# Adafruit_VS1053_Amp_FeatherWing.net
KiCad netlist of a schematic drawn in EAGLE
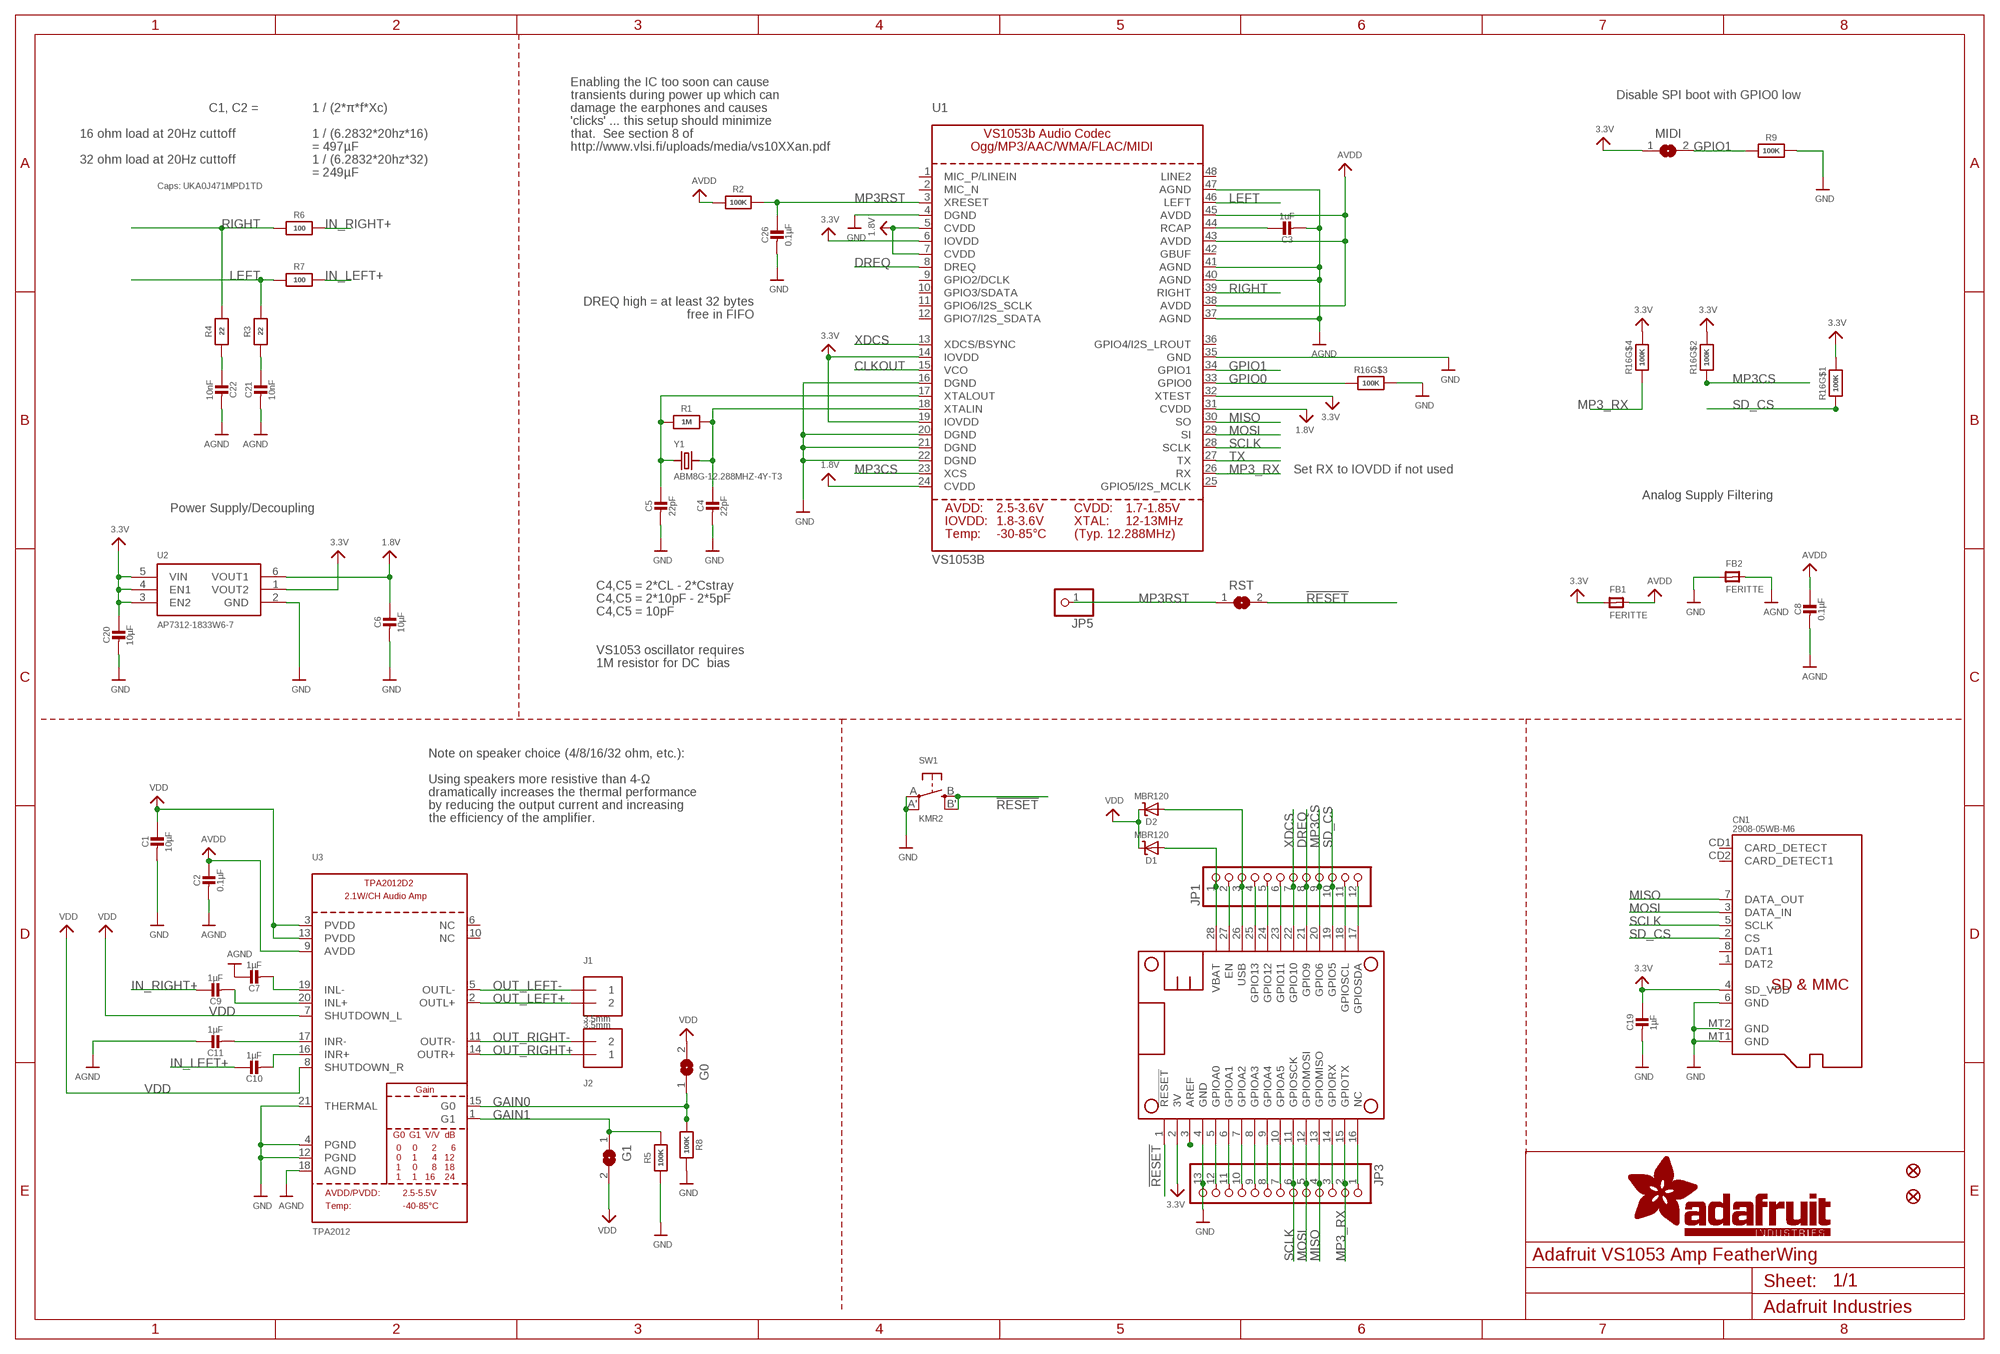
[diagram p0: schematic, sheet 1]

(export (version "E")
  (design (tool "Eeschema 10.0.6"))
  (components
    (comp (ref "C1")
      (value "10µF")
      (footprint "eagle-import:0805-NO")
      (libsource (lib "eagle-import") (part "CAP_CERAMIC0805-NOOUTLINE"))
    )
    (comp (ref "C2")
      (value "0.1µF")
      (footprint "eagle-import:0603-NO")
      (libsource (lib "eagle-import") (part "CAP_CERAMIC0603_NO"))
    )
    (comp (ref "C3")
      (value "1uF")
      (footprint "eagle-import:0603-NO")
      (libsource (lib "eagle-import") (part "CAP_CERAMIC0603_NO"))
    )
    (comp (ref "C4")
      (value "22pF")
      (footprint "eagle-import:0603-NO")
      (libsource (lib "eagle-import") (part "CAP_CERAMIC0603_NO"))
    )
    (comp (ref "C5")
      (value "22pF")
      (footprint "eagle-import:0603-NO")
      (libsource (lib "eagle-import") (part "CAP_CERAMIC0603_NO"))
    )
    (comp (ref "C6")
      (value "10µF")
      (footprint "eagle-import:_0805MP")
      (libsource (lib "eagle-import") (part "CAP_CERAMIC_0805MP"))
    )
    (comp (ref "C7")
      (value "1µF")
      (footprint "eagle-import:0603-NO")
      (libsource (lib "eagle-import") (part "CAP_CERAMIC0603_NO"))
    )
    (comp (ref "C8")
      (value "0.1µF")
      (footprint "eagle-import:0603-NO")
      (libsource (lib "eagle-import") (part "CAP_CERAMIC0603_NO"))
    )
    (comp (ref "C9")
      (value "1µF")
      (footprint "eagle-import:0603-NO")
      (libsource (lib "eagle-import") (part "CAP_CERAMIC0603_NO"))
    )
    (comp (ref "C10")
      (value "1µF")
      (footprint "eagle-import:0603-NO")
      (libsource (lib "eagle-import") (part "CAP_CERAMIC0603_NO"))
    )
    (comp (ref "C11")
      (value "1µF")
      (footprint "eagle-import:0603-NO")
      (libsource (lib "eagle-import") (part "CAP_CERAMIC0603_NO"))
    )
    (comp (ref "C19")
      (value "1µF")
      (footprint "eagle-import:0603-NO")
      (libsource (lib "eagle-import") (part "CAP_CERAMIC0603_NO"))
    )
    (comp (ref "C20")
      (value "10µF")
      (footprint "eagle-import:0805-NO")
      (libsource (lib "eagle-import") (part "CAP_CERAMIC0805-NOOUTLINE"))
    )
    (comp (ref "C21")
      (value "10nF")
      (footprint "eagle-import:0603-NO")
      (libsource (lib "eagle-import") (part "CAP_CERAMIC0603_NO"))
    )
    (comp (ref "C22")
      (value "10nF")
      (footprint "eagle-import:0603-NO")
      (libsource (lib "eagle-import") (part "CAP_CERAMIC0603_NO"))
    )
    (comp (ref "C26")
      (value "0.1µF")
      (footprint "eagle-import:0603-NO")
      (libsource (lib "eagle-import") (part "CAP_CERAMIC0603_NO"))
    )
    (comp (ref "CN1")
      (value "2908-05WB-M6")
      (footprint "eagle-import:MICROSD")
      (libsource (lib "eagle-import") (part "MICROSD"))
    )
    (comp (ref "D1")
      (value "MBR120")
      (footprint "eagle-import:SOD-123")
      (libsource (lib "eagle-import") (part "DIODE-SCHOTTKYSOD-123"))
    )
    (comp (ref "D2")
      (value "MBR120")
      (footprint "eagle-import:SOD-123")
      (libsource (lib "eagle-import") (part "DIODE-SCHOTTKYSOD-123"))
    )
    (comp (ref "FB1")
      (value "FERITTE")
      (footprint "eagle-import:0805-NO")
      (libsource (lib "eagle-import") (part "FERRITE-0805NO"))
    )
    (comp (ref "FB2")
      (value "FERITTE")
      (footprint "eagle-import:0805-NO")
      (libsource (lib "eagle-import") (part "FERRITE-0805NO"))
    )
    (comp (ref "FID1")
      (value "FIDUCIAL\"\"")
      (footprint "eagle-import:FIDUCIAL_1MM")
      (libsource (lib "eagle-import") (part "FIDUCIAL{dblquote}{dblquote}"))
    )
    (comp (ref "FID2")
      (value "FIDUCIAL\"\"")
      (footprint "eagle-import:FIDUCIAL_1MM")
      (libsource (lib "eagle-import") (part "FIDUCIAL{dblquote}{dblquote}"))
    )
    (comp (ref "G0")
      (value "SOLDERJUMPER")
      (footprint "eagle-import:SOLDERJUMPER_ARROW_NOPASTE")
      (libsource (lib "eagle-import") (part "SOLDERJUMPER"))
    )
    (comp (ref "G1")
      (value "SOLDERJUMPER")
      (footprint "eagle-import:SOLDERJUMPER_ARROW_NOPASTE")
      (libsource (lib "eagle-import") (part "SOLDERJUMPER"))
    )
    (comp (ref "J1")
      (value "3.5mm")
      (footprint "eagle-import:TERMBLOCK_1X2-3.5MM")
      (libsource (lib "eagle-import") (part "TERMBLOCK_1X2"))
    )
    (comp (ref "J2")
      (value "3.5mm")
      (footprint "eagle-import:TERMBLOCK_1X2-3.5MM")
      (libsource (lib "eagle-import") (part "TERMBLOCK_1X2"))
    )
    (comp (ref "JP1")
      (value "HEADER-1X12")
      (footprint "eagle-import:1X12_ROUND")
      (libsource (lib "eagle-import") (part "HEADER-1X12"))
    )
    (comp (ref "JP3")
      (value "HEADER-1X13")
      (footprint "eagle-import:1X13_ROUND_70")
      (libsource (lib "eagle-import") (part "HEADER-1X13"))
    )
    (comp (ref "JP5")
      (value "HEADER-1X1ROUND")
      (footprint "eagle-import:1X01_ROUND")
      (libsource (lib "eagle-import") (part "HEADER-1X1ROUND"))
    )
    (comp (ref "MIDI")
      (value "SOLDERJUMPER")
      (footprint "eagle-import:SOLDERJUMPER_ARROW_NOPASTE")
      (libsource (lib "eagle-import") (part "SOLDERJUMPER"))
    )
    (comp (ref "MS1")
      (value "FEATHERWING_NODIM")
      (footprint "eagle-import:FEATHERWING_NODIM")
      (libsource (lib "eagle-import") (part "FEATHERWING_NODIM"))
    )
    (comp (ref "R1")
      (value "1M")
      (footprint "eagle-import:0603-NO")
      (libsource (lib "eagle-import") (part "RESISTOR_0603_NOOUT"))
    )
    (comp (ref "R2")
      (value "100K")
      (footprint "eagle-import:0603-NO")
      (libsource (lib "eagle-import") (part "RESISTOR_0603_NOOUT"))
    )
    (comp (ref "R3")
      (value "22")
      (footprint "eagle-import:0603-NO")
      (libsource (lib "eagle-import") (part "RESISTOR_0603_NOOUT"))
    )
    (comp (ref "R4")
      (value "22")
      (footprint "eagle-import:0603-NO")
      (libsource (lib "eagle-import") (part "RESISTOR_0603_NOOUT"))
    )
    (comp (ref "R5")
      (value "100K")
      (footprint "eagle-import:0603-NO")
      (libsource (lib "eagle-import") (part "RESISTOR_0603_NOOUT"))
    )
    (comp (ref "R6")
      (value "100")
      (footprint "eagle-import:0603-NO")
      (libsource (lib "eagle-import") (part "RESISTOR_0603_NOOUT"))
    )
    (comp (ref "R7")
      (value "100")
      (footprint "eagle-import:0603-NO")
      (libsource (lib "eagle-import") (part "RESISTOR_0603_NOOUT"))
    )
    (comp (ref "R8")
      (value "100K")
      (footprint "eagle-import:0603-NO")
      (libsource (lib "eagle-import") (part "RESISTOR_0603_NOOUT"))
    )
    (comp (ref "R9")
      (value "100K")
      (footprint "eagle-import:_0603MP")
      (libsource (lib "eagle-import") (part "RESISTOR_0603MP"))
    )
    (comp (ref "R16")
      (value "100K")
      (footprint "eagle-import:RESPACK_4X0603")
      (libsource (lib "eagle-import") (part "RESISTOR_4PACK"))
    )
    (comp (ref "RST")
      (value "SOLDERJUMPERCLOSED")
      (footprint "eagle-import:SOLDERJUMPER_CLOSEDWIRE")
      (libsource (lib "eagle-import") (part "SOLDERJUMPERCLOSED"))
    )
    (comp (ref "SW1")
      (value "KMR2")
      (footprint "eagle-import:BTN_KMR2_4.6X2.8")
      (libsource (lib "eagle-import") (part "SWITCH_TACT_SMT4.6X2.8"))
    )
    (comp (ref "U1")
      (value "VS1053B")
      (footprint "eagle-import:LQFP48")
      (libsource (lib "eagle-import") (part "VS1053B"))
    )
    (comp (ref "U2")
      (value "AP7312-1833W6-7")
      (footprint "eagle-import:SOT23-6")
      (libsource (lib "eagle-import") (part "VREG_SOT23-6_DUALAP7312"))
    )
    (comp (ref "U3")
      (value "TPA2012")
      (footprint "eagle-import:WQFN20")
      (libsource (lib "eagle-import") (part "AUDIOAMP_TPA2012D2"))
    )
    (comp (ref "Y1")
      (value "ABM8G-12.288MHZ-4Y-T3")
      (footprint "eagle-import:CRYSTAL_3.2X2.5")
      (libsource (lib "eagle-import") (part "CRYSTAL3.2X2.5"))
    )
  )
  (nets
    (net (code "1") (name "/CLKOUT") (class "Default")
      (node (ref "U1") (pin "15") (pinfunction "VCO_15") (pintype "bidirectional"))
    )
    (net (code "2") (name "/DREQ") (class "Default")
      (node (ref "JP1") (pin "8") (pinfunction "8_8") (pintype "passive"))
      (node (ref "MS1") (pin "21") (pinfunction "GPIO9_21") (pintype "bidirectional"))
      (node (ref "U1") (pin "8") (pinfunction "DREQ_8") (pintype "bidirectional"))
    )
    (net (code "3") (name "/GAIN0") (class "Default")
      (node (ref "G0") (pin "1") (pinfunction "1_1") (pintype "passive"))
      (node (ref "R8") (pin "1") (pinfunction "1_1") (pintype "passive"))
      (node (ref "U3") (pin "15") (pinfunction "G0_15") (pintype "input"))
    )
    (net (code "4") (name "/GAIN1") (class "Default")
      (node (ref "G1") (pin "1") (pinfunction "1_1") (pintype "passive"))
      (node (ref "R5") (pin "2") (pinfunction "2_2") (pintype "passive"))
      (node (ref "U3") (pin "1") (pinfunction "G1_1") (pintype "input"))
    )
    (net (code "5") (name "/GPIO0") (class "Default")
      (node (ref "R16") (pin "3") (pinfunction "1_3") (pintype "passive"))
      (node (ref "U1") (pin "33") (pinfunction "GPIO0_33") (pintype "bidirectional"))
    )
    (net (code "6") (name "/GPIO1") (class "Default")
      (node (ref "MIDI") (pin "2") (pinfunction "2_2") (pintype "passive"))
      (node (ref "R9") (pin "1") (pinfunction "1_1") (pintype "passive"))
      (node (ref "U1") (pin "34") (pinfunction "GPIO1_34") (pintype "bidirectional"))
    )
    (net (code "7") (name "/IN_LEFT+") (class "Default")
      (node (ref "C10") (pin "1") (pinfunction "1_1") (pintype "passive"))
      (node (ref "R7") (pin "1") (pinfunction "1_1") (pintype "passive"))
    )
    (net (code "8") (name "/IN_RIGHT+") (class "Default")
      (node (ref "C9") (pin "1") (pinfunction "1_1") (pintype "passive"))
      (node (ref "R6") (pin "1") (pinfunction "1_1") (pintype "passive"))
    )
    (net (code "9") (name "/LEFT") (class "Default")
      (node (ref "R3") (pin "1") (pinfunction "1_1") (pintype "passive"))
      (node (ref "R7") (pin "2") (pinfunction "2_2") (pintype "passive"))
      (node (ref "U1") (pin "46") (pinfunction "LEFT_46") (pintype "bidirectional"))
    )
    (net (code "10") (name "/MISO") (class "Default")
      (node (ref "CN1") (pin "7") (pinfunction "DATA_OUT_7") (pintype "output"))
      (node (ref "JP3") (pin "4") (pinfunction "4_4") (pintype "passive"))
      (node (ref "MS1") (pin "13") (pinfunction "GPIOMISO_13") (pintype "bidirectional"))
      (node (ref "U1") (pin "30") (pinfunction "SO_30") (pintype "bidirectional"))
    )
    (net (code "11") (name "/MOSI") (class "Default")
      (node (ref "CN1") (pin "3") (pinfunction "DATA_IN_3") (pintype "input"))
      (node (ref "JP3") (pin "5") (pinfunction "5_5") (pintype "passive"))
      (node (ref "MS1") (pin "12") (pinfunction "GPIOMOSI_12") (pintype "bidirectional"))
      (node (ref "U1") (pin "29") (pinfunction "SI_29") (pintype "bidirectional"))
    )
    (net (code "12") (name "/MP3CS") (class "Default")
      (node (ref "JP1") (pin "9") (pinfunction "9_9") (pintype "passive"))
      (node (ref "MS1") (pin "20") (pinfunction "GPIO6_20") (pintype "bidirectional"))
      (node (ref "R16") (pin "2") (pinfunction "1_2") (pintype "passive"))
      (node (ref "U1") (pin "23") (pinfunction "XCS_23") (pintype "bidirectional"))
    )
    (net (code "13") (name "/MP3RST") (class "Default")
      (node (ref "C26") (pin "1") (pinfunction "1_1") (pintype "passive"))
      (node (ref "JP5") (pin "1") (pinfunction "1_1") (pintype "passive"))
      (node (ref "R2") (pin "2") (pinfunction "2_2") (pintype "passive"))
      (node (ref "RST") (pin "1") (pinfunction "1_1") (pintype "passive"))
      (node (ref "U1") (pin "3") (pinfunction "XRESET_3") (pintype "bidirectional"))
    )
    (net (code "14") (name "/MP3_RX") (class "Default")
      (node (ref "JP3") (pin "2") (pinfunction "2_2") (pintype "passive"))
      (node (ref "MS1") (pin "15") (pinfunction "GPIOTX_15") (pintype "bidirectional"))
      (node (ref "R16") (pin "4") (pinfunction "1_4") (pintype "passive"))
      (node (ref "U1") (pin "26") (pinfunction "RX_26") (pintype "bidirectional"))
    )
    (net (code "15") (name "/OUT_LEFT+") (class "Default")
      (node (ref "J1") (pin "2") (pinfunction "2_2") (pintype "passive"))
      (node (ref "U3") (pin "2") (pinfunction "OUTL+_2") (pintype "output"))
    )
    (net (code "16") (name "/OUT_LEFT-") (class "Default")
      (node (ref "J1") (pin "1") (pinfunction "1_1") (pintype "passive"))
      (node (ref "U3") (pin "5") (pinfunction "OUTL-_5") (pintype "output"))
    )
    (net (code "17") (name "/OUT_RIGHT+") (class "Default")
      (node (ref "J2") (pin "1") (pinfunction "1_1") (pintype "passive"))
      (node (ref "U3") (pin "14") (pinfunction "OUTR+_14") (pintype "output"))
    )
    (net (code "18") (name "/OUT_RIGHT-") (class "Default")
      (node (ref "J2") (pin "2") (pinfunction "2_2") (pintype "passive"))
      (node (ref "U3") (pin "11") (pinfunction "OUTR-_11") (pintype "output"))
    )
    (net (code "19") (name "/RIGHT") (class "Default")
      (node (ref "R4") (pin "1") (pinfunction "1_1") (pintype "passive"))
      (node (ref "R6") (pin "2") (pinfunction "2_2") (pintype "passive"))
      (node (ref "U1") (pin "39") (pinfunction "RIGHT_39") (pintype "bidirectional"))
    )
    (net (code "20") (name "/SCLK") (class "Default")
      (node (ref "CN1") (pin "5") (pinfunction "SCLK_5") (pintype "input"))
      (node (ref "JP3") (pin "6") (pinfunction "6_6") (pintype "passive"))
      (node (ref "MS1") (pin "11") (pinfunction "GPIOSCK_11") (pintype "bidirectional"))
      (node (ref "U1") (pin "28") (pinfunction "SCLK_28") (pintype "bidirectional"))
    )
    (net (code "21") (name "/SD_CS") (class "Default")
      (node (ref "CN1") (pin "2") (pinfunction "CS_2") (pintype "input"))
      (node (ref "JP1") (pin "10") (pinfunction "10_10") (pintype "passive"))
      (node (ref "MS1") (pin "19") (pinfunction "GPIO5_19") (pintype "bidirectional"))
      (node (ref "R16") (pin "1") (pinfunction "1_1") (pintype "passive"))
    )
    (net (code "22") (name "/TX") (class "Default")
      (node (ref "U1") (pin "27") (pinfunction "TX_27") (pintype "bidirectional"))
    )
    (net (code "23") (name "/XDCS") (class "Default")
      (node (ref "JP1") (pin "7") (pinfunction "7_7") (pintype "passive"))
      (node (ref "MS1") (pin "22") (pinfunction "GPIO10_22") (pintype "bidirectional"))
      (node (ref "U1") (pin "13") (pinfunction "XDCS/BSYNC_13") (pintype "bidirectional"))
    )
    (net (code "24") (name "/~{RESET}") (class "Default")
      (node (ref "MS1") (pin "1") (pinfunction "~{RESET}_1") (pintype "input"))
      (node (ref "RST") (pin "2") (pinfunction "2_2") (pintype "passive"))
      (node (ref "SW1") (pin "B") (pinfunction "S_B") (pintype "passive"))
      (node (ref "SW1") (pin "B'") (pinfunction "S1_B'") (pintype "passive"))
    )
    (net (code "25") (name "1.8V") (class "Default")
      (node (ref "C6") (pin "1") (pinfunction "1_1") (pintype "passive"))
      (node (ref "U1") (pin "24") (pinfunction "CVDD_24") (pintype "power_in"))
      (node (ref "U1") (pin "31") (pinfunction "CVDD_31") (pintype "power_in"))
      (node (ref "U1") (pin "5") (pinfunction "CVDD_5") (pintype "power_in"))
      (node (ref "U1") (pin "7") (pinfunction "CVDD_7") (pintype "power_in"))
      (node (ref "U2") (pin "6") (pinfunction "VOUT1_6") (pintype "bidirectional"))
    )
    (net (code "26") (name "3.3V") (class "Default")
      (node (ref "C19") (pin "1") (pinfunction "1_1") (pintype "passive"))
      (node (ref "C20") (pin "1") (pinfunction "1_1") (pintype "passive"))
      (node (ref "CN1") (pin "4") (pinfunction "SD_VDD_4") (pintype "power_in"))
      (node (ref "FB1") (pin "1") (pinfunction "P$1_1") (pintype "passive"))
      (node (ref "MIDI") (pin "1") (pinfunction "1_1") (pintype "passive"))
      (node (ref "MS1") (pin "2") (pinfunction "3V_2") (pintype "power_in"))
      (node (ref "R16") (pin "5") (pinfunction "2_5") (pintype "passive"))
      (node (ref "R16") (pin "7") (pinfunction "2_7") (pintype "passive"))
      (node (ref "R16") (pin "8") (pinfunction "2_8") (pintype "passive"))
      (node (ref "U1") (pin "14") (pinfunction "IOVDD_14") (pintype "power_in"))
      (node (ref "U1") (pin "19") (pinfunction "IOVDD_19") (pintype "power_in"))
      (node (ref "U1") (pin "32") (pinfunction "XTEST_32") (pintype "bidirectional"))
      (node (ref "U1") (pin "6") (pinfunction "IOVDD_6") (pintype "power_in"))
      (node (ref "U2") (pin "1") (pinfunction "VOUT2_1") (pintype "bidirectional"))
      (node (ref "U2") (pin "3") (pinfunction "EN2_3") (pintype "bidirectional"))
      (node (ref "U2") (pin "4") (pinfunction "EN1_4") (pintype "bidirectional"))
      (node (ref "U2") (pin "5") (pinfunction "VIN_5") (pintype "bidirectional"))
    )
    (net (code "27") (name "AGND") (class "Default")
      (node (ref "C11") (pin "1") (pinfunction "1_1") (pintype "passive"))
      (node (ref "C2") (pin "2") (pinfunction "2_2") (pintype "passive"))
      (node (ref "C21") (pin "2") (pinfunction "2_2") (pintype "passive"))
      (node (ref "C22") (pin "2") (pinfunction "2_2") (pintype "passive"))
      (node (ref "C3") (pin "2") (pinfunction "2_2") (pintype "passive"))
      (node (ref "C7") (pin "1") (pinfunction "1_1") (pintype "passive"))
      (node (ref "C8") (pin "2") (pinfunction "2_2") (pintype "passive"))
      (node (ref "FB2") (pin "2") (pinfunction "P$2_2") (pintype "passive"))
      (node (ref "U1") (pin "37") (pinfunction "AGND_37") (pintype "power_in"))
      (node (ref "U1") (pin "40") (pinfunction "AGND_40") (pintype "power_in"))
      (node (ref "U1") (pin "41") (pinfunction "AGND_41") (pintype "power_in"))
      (node (ref "U1") (pin "47") (pinfunction "AGND_47") (pintype "power_in"))
      (node (ref "U3") (pin "18") (pinfunction "AGND_18") (pintype "power_in"))
    )
    (net (code "28") (name "AVDD") (class "Default")
      (node (ref "C2") (pin "1") (pinfunction "1_1") (pintype "passive"))
      (node (ref "C8") (pin "1") (pinfunction "1_1") (pintype "passive"))
      (node (ref "FB1") (pin "2") (pinfunction "P$2_2") (pintype "passive"))
      (node (ref "R2") (pin "1") (pinfunction "1_1") (pintype "passive"))
      (node (ref "U1") (pin "38") (pinfunction "AVDD_38") (pintype "power_in"))
      (node (ref "U1") (pin "43") (pinfunction "AVDD_43") (pintype "power_in"))
      (node (ref "U1") (pin "45") (pinfunction "AVDD_45") (pintype "power_in"))
      (node (ref "U3") (pin "9") (pinfunction "AVDD_9") (pintype "power_in"))
    )
    (net (code "29") (name "GND") (class "Default")
      (node (ref "C1") (pin "2") (pinfunction "2_2") (pintype "passive"))
      (node (ref "C19") (pin "2") (pinfunction "2_2") (pintype "passive"))
      (node (ref "C20") (pin "2") (pinfunction "2_2") (pintype "passive"))
      (node (ref "C26") (pin "2") (pinfunction "2_2") (pintype "passive"))
      (node (ref "C4") (pin "2") (pinfunction "2_2") (pintype "passive"))
      (node (ref "C5") (pin "2") (pinfunction "2_2") (pintype "passive"))
      (node (ref "C6") (pin "2") (pinfunction "2_2") (pintype "passive"))
      (node (ref "CN1") (pin "6") (pinfunction "GND_6") (pintype "power_in"))
      (node (ref "CN1") (pin "MT1") (pinfunction "GND_MT1") (pintype "power_in"))
      (node (ref "CN1") (pin "MT2") (pinfunction "GND_MT2") (pintype "power_in"))
      (node (ref "FB2") (pin "1") (pinfunction "P$1_1") (pintype "passive"))
      (node (ref "JP3") (pin "13") (pinfunction "13_13") (pintype "passive"))
      (node (ref "MS1") (pin "4") (pinfunction "GND_4") (pintype "power_in"))
      (node (ref "R16") (pin "6") (pinfunction "2_6") (pintype "passive"))
      (node (ref "R5") (pin "1") (pinfunction "1_1") (pintype "passive"))
      (node (ref "R8") (pin "2") (pinfunction "2_2") (pintype "passive"))
      (node (ref "R9") (pin "2") (pinfunction "2_2") (pintype "passive"))
      (node (ref "SW1") (pin "A") (pinfunction "P_A") (pintype "passive"))
      (node (ref "SW1") (pin "A'") (pinfunction "P1_A'") (pintype "passive"))
      (node (ref "U1") (pin "16") (pinfunction "DGND_16") (pintype "power_in"))
      (node (ref "U1") (pin "20") (pinfunction "DGND_20") (pintype "power_in"))
      (node (ref "U1") (pin "21") (pinfunction "DGND_21") (pintype "power_in"))
      (node (ref "U1") (pin "22") (pinfunction "DGND_22") (pintype "power_in"))
      (node (ref "U1") (pin "35") (pinfunction "GND_35") (pintype "power_in"))
      (node (ref "U1") (pin "4") (pinfunction "DGND_4") (pintype "power_in"))
      (node (ref "U2") (pin "2") (pinfunction "GND_2") (pintype "bidirectional"))
      (node (ref "U3") (pin "12") (pinfunction "PGND_12") (pintype "power_in"))
      (node (ref "U3") (pin "21") (pinfunction "THERMAL_21") (pintype "bidirectional"))
      (node (ref "U3") (pin "4") (pinfunction "PGND_4") (pintype "power_in"))
    )
    (net (code "30") (name "Net-(C21-Pad1)") (class "Default")
      (node (ref "C21") (pin "1") (pinfunction "1_1") (pintype "passive"))
      (node (ref "R3") (pin "2") (pinfunction "2_2") (pintype "passive"))
    )
    (net (code "31") (name "Net-(C22-Pad1)") (class "Default")
      (node (ref "C22") (pin "1") (pinfunction "1_1") (pintype "passive"))
      (node (ref "R4") (pin "2") (pinfunction "2_2") (pintype "passive"))
    )
    (net (code "32") (name "Net-(MS1-EN)") (class "Default")
      (node (ref "JP1") (pin "2") (pinfunction "2_2") (pintype "passive"))
      (node (ref "MS1") (pin "27") (pinfunction "EN_27") (pintype "passive"))
    )
    (net (code "33") (name "Net-(MS1-GPIO11)") (class "Default")
      (node (ref "JP1") (pin "6") (pinfunction "6_6") (pintype "passive"))
      (node (ref "MS1") (pin "23") (pinfunction "GPIO11_23") (pintype "bidirectional"))
    )
    (net (code "34") (name "Net-(MS1-GPIO12)") (class "Default")
      (node (ref "JP1") (pin "5") (pinfunction "5_5") (pintype "passive"))
      (node (ref "MS1") (pin "24") (pinfunction "GPIO12_24") (pintype "bidirectional"))
    )
    (net (code "35") (name "Net-(MS1-GPIO13)") (class "Default")
      (node (ref "JP1") (pin "4") (pinfunction "4_4") (pintype "passive"))
      (node (ref "MS1") (pin "25") (pinfunction "GPIO13_25") (pintype "bidirectional"))
    )
    (net (code "36") (name "Net-(MS1-GPIOA0)") (class "Default")
      (node (ref "JP3") (pin "12") (pinfunction "12_12") (pintype "passive"))
      (node (ref "MS1") (pin "5") (pinfunction "GPIOA0_5") (pintype "bidirectional"))
    )
    (net (code "37") (name "Net-(MS1-GPIOA1)") (class "Default")
      (node (ref "JP3") (pin "11") (pinfunction "11_11") (pintype "passive"))
      (node (ref "MS1") (pin "6") (pinfunction "GPIOA1_6") (pintype "bidirectional"))
    )
    (net (code "38") (name "Net-(MS1-GPIOA2)") (class "Default")
      (node (ref "JP3") (pin "10") (pinfunction "10_10") (pintype "passive"))
      (node (ref "MS1") (pin "7") (pinfunction "GPIOA2_7") (pintype "bidirectional"))
    )
    (net (code "39") (name "Net-(MS1-GPIOA3)") (class "Default")
      (node (ref "JP3") (pin "9") (pinfunction "9_9") (pintype "passive"))
      (node (ref "MS1") (pin "8") (pinfunction "GPIOA3_8") (pintype "bidirectional"))
    )
    (net (code "40") (name "Net-(MS1-GPIOA4)") (class "Default")
      (node (ref "JP3") (pin "8") (pinfunction "8_8") (pintype "passive"))
      (node (ref "MS1") (pin "9") (pinfunction "GPIOA4_9") (pintype "bidirectional"))
    )
    (net (code "41") (name "Net-(MS1-GPIOA5)") (class "Default")
      (node (ref "JP3") (pin "7") (pinfunction "7_7") (pintype "passive"))
      (node (ref "MS1") (pin "10") (pinfunction "GPIOA5_10") (pintype "bidirectional"))
    )
    (net (code "42") (name "Net-(MS1-GPIORX)") (class "Default")
      (node (ref "JP3") (pin "3") (pinfunction "3_3") (pintype "passive"))
      (node (ref "MS1") (pin "14") (pinfunction "GPIORX_14") (pintype "bidirectional"))
    )
    (net (code "43") (name "Net-(MS1-GPIOSCL)") (class "Default")
      (node (ref "JP1") (pin "11") (pinfunction "11_11") (pintype "passive"))
      (node (ref "MS1") (pin "18") (pinfunction "GPIOSCL_18") (pintype "bidirectional"))
    )
    (net (code "44") (name "Net-(MS1-GPIOSDA)") (class "Default")
      (node (ref "JP1") (pin "12") (pinfunction "12_12") (pintype "passive"))
      (node (ref "MS1") (pin "17") (pinfunction "GPIOSDA_17") (pintype "bidirectional"))
    )
    (net (code "45") (name "Net-(MS1-NC)") (class "Default")
      (node (ref "JP3") (pin "1") (pinfunction "1_1") (pintype "passive"))
      (node (ref "MS1") (pin "16") (pinfunction "NC_16") (pintype "passive"))
    )
    (net (code "46") (name "Net-(MS1-USB)") (class "Default")
      (node (ref "D2") (pin "A") (pinfunction "A_A") (pintype "passive"))
      (node (ref "JP1") (pin "3") (pinfunction "3_3") (pintype "passive"))
      (node (ref "MS1") (pin "26") (pinfunction "USB_26") (pintype "power_in"))
    )
    (net (code "47") (name "Net-(MS1-VBAT)") (class "Default")
      (node (ref "D1") (pin "A") (pinfunction "A_A") (pintype "passive"))
      (node (ref "JP1") (pin "1") (pinfunction "1_1") (pintype "passive"))
      (node (ref "MS1") (pin "28") (pinfunction "VBAT_28") (pintype "power_in"))
    )
    (net (code "48") (name "Net-(U1-RCAP)") (class "Default")
      (node (ref "C3") (pin "1") (pinfunction "1_1") (pintype "passive"))
      (node (ref "U1") (pin "44") (pinfunction "RCAP_44") (pintype "bidirectional"))
    )
    (net (code "49") (name "Net-(U1-XTALIN)") (class "Default")
      (node (ref "C4") (pin "1") (pinfunction "1_1") (pintype "passive"))
      (node (ref "R1") (pin "2") (pinfunction "2_2") (pintype "passive"))
      (node (ref "U1") (pin "18") (pinfunction "XTALIN_18") (pintype "input"))
      (node (ref "Y1") (pin "2") (pinfunction "2_2") (pintype "passive"))
    )
    (net (code "50") (name "Net-(U1-XTALOUT)") (class "Default")
      (node (ref "C5") (pin "1") (pinfunction "1_1") (pintype "passive"))
      (node (ref "R1") (pin "1") (pinfunction "1_1") (pintype "passive"))
      (node (ref "U1") (pin "17") (pinfunction "XTALOUT_17") (pintype "output"))
      (node (ref "Y1") (pin "1") (pinfunction "1_1") (pintype "passive"))
    )
    (net (code "51") (name "Net-(U3-INL+)") (class "Default")
      (node (ref "C9") (pin "2") (pinfunction "2_2") (pintype "passive"))
      (node (ref "U3") (pin "20") (pinfunction "INL+_20") (pintype "input"))
    )
    (net (code "52") (name "Net-(U3-INL-)") (class "Default")
      (node (ref "C7") (pin "2") (pinfunction "2_2") (pintype "passive"))
      (node (ref "U3") (pin "19") (pinfunction "INL-_19") (pintype "input"))
    )
    (net (code "53") (name "Net-(U3-INR+)") (class "Default")
      (node (ref "C10") (pin "2") (pinfunction "2_2") (pintype "passive"))
      (node (ref "U3") (pin "16") (pinfunction "INR+_16") (pintype "input"))
    )
    (net (code "54") (name "Net-(U3-INR-)") (class "Default")
      (node (ref "C11") (pin "2") (pinfunction "2_2") (pintype "passive"))
      (node (ref "U3") (pin "17") (pinfunction "INR-_17") (pintype "input"))
    )
    (net (code "55") (name "VDD") (class "Default")
      (node (ref "C1") (pin "1") (pinfunction "1_1") (pintype "passive"))
      (node (ref "D1") (pin "C") (pinfunction "C_C") (pintype "passive"))
      (node (ref "D2") (pin "C") (pinfunction "C_C") (pintype "passive"))
      (node (ref "G0") (pin "2") (pinfunction "2_2") (pintype "passive"))
      (node (ref "G1") (pin "2") (pinfunction "2_2") (pintype "passive"))
      (node (ref "U3") (pin "13") (pinfunction "PVDD_13") (pintype "power_in"))
      (node (ref "U3") (pin "3") (pinfunction "PVDD_3") (pintype "power_in"))
      (node (ref "U3") (pin "7") (pinfunction "SHUTDOWN_L_7") (pintype "input"))
      (node (ref "U3") (pin "8") (pinfunction "SHUTDOWN_R_8") (pintype "input"))
    )
    (net (code "56") (name "unconnected-(CN1-CARD_DETECT-PadCD1)") (class "Default")
      (node (ref "CN1") (pin "CD1") (pinfunction "CARD_DETECT_CD1") (pintype "passive"))
    )
    (net (code "57") (name "unconnected-(CN1-CARD_DETECT1-PadCD2)") (class "Default")
      (node (ref "CN1") (pin "CD2") (pinfunction "CARD_DETECT1_CD2") (pintype "passive"))
    )
    (net (code "58") (name "unconnected-(CN1-DAT1-Pad8)") (class "Default")
      (node (ref "CN1") (pin "8") (pinfunction "DAT1_8") (pintype "bidirectional"))
    )
    (net (code "59") (name "unconnected-(CN1-DAT2-Pad1)") (class "Default")
      (node (ref "CN1") (pin "1") (pinfunction "DAT2_1") (pintype "bidirectional"))
    )
    (net (code "60") (name "unconnected-(MS1-AREF-Pad3)") (class "Default")
      (node (ref "MS1") (pin "3") (pinfunction "AREF_3") (pintype "passive"))
    )
    (net (code "61") (name "unconnected-(U1-GBUF-Pad42)") (class "Default")
      (node (ref "U1") (pin "42") (pinfunction "GBUF_42") (pintype "bidirectional"))
    )
    (net (code "62") (name "unconnected-(U1-GPIO2{slash}DCLK-Pad9)") (class "Default")
      (node (ref "U1") (pin "9") (pinfunction "GPIO2/DCLK_9") (pintype "bidirectional"))
    )
    (net (code "63") (name "unconnected-(U1-GPIO3{slash}SDATA-Pad10)") (class "Default")
      (node (ref "U1") (pin "10") (pinfunction "GPIO3/SDATA_10") (pintype "bidirectional"))
    )
    (net (code "64") (name "unconnected-(U1-GPIO4{slash}I2S_LROUT-Pad36)") (class "Default")
      (node (ref "U1") (pin "36") (pinfunction "GPIO4/I2S_LROUT_36") (pintype "bidirectional"))
    )
    (net (code "65") (name "unconnected-(U1-GPIO5{slash}I2S_MCLK-Pad25)") (class "Default")
      (node (ref "U1") (pin "25") (pinfunction "GPIO5/I2S_MCLK_25") (pintype "bidirectional"))
    )
    (net (code "66") (name "unconnected-(U1-GPIO6{slash}I2S_SCLK-Pad11)") (class "Default")
      (node (ref "U1") (pin "11") (pinfunction "GPIO6/I2S_SCLK_11") (pintype "bidirectional"))
    )
    (net (code "67") (name "unconnected-(U1-GPIO7{slash}I2S_SDATA-Pad12)") (class "Default")
      (node (ref "U1") (pin "12") (pinfunction "GPIO7/I2S_SDATA_12") (pintype "bidirectional"))
    )
    (net (code "68") (name "unconnected-(U1-LINE2-Pad48)") (class "Default")
      (node (ref "U1") (pin "48") (pinfunction "LINE2_48") (pintype "bidirectional"))
    )
    (net (code "69") (name "unconnected-(U1-MIC_N-Pad2)") (class "Default")
      (node (ref "U1") (pin "2") (pinfunction "MIC_N_2") (pintype "bidirectional"))
    )
    (net (code "70") (name "unconnected-(U1-MIC_P{slash}LINEIN-Pad1)") (class "Default")
      (node (ref "U1") (pin "1") (pinfunction "MIC_P/LINEIN_1") (pintype "bidirectional"))
    )
    (net (code "71") (name "unconnected-(U3-NC-Pad6)") (class "Default")
      (node (ref "U3") (pin "6") (pinfunction "NC_6") (pintype "no_connect"))
    )
    (net (code "72") (name "unconnected-(U3-NC-Pad10)") (class "Default")
      (node (ref "U3") (pin "10") (pinfunction "NC_10") (pintype "no_connect"))
    )
  )
)
